# LDO_3V3.net
KiCad netlist of a schematic drawn in Altium Designer
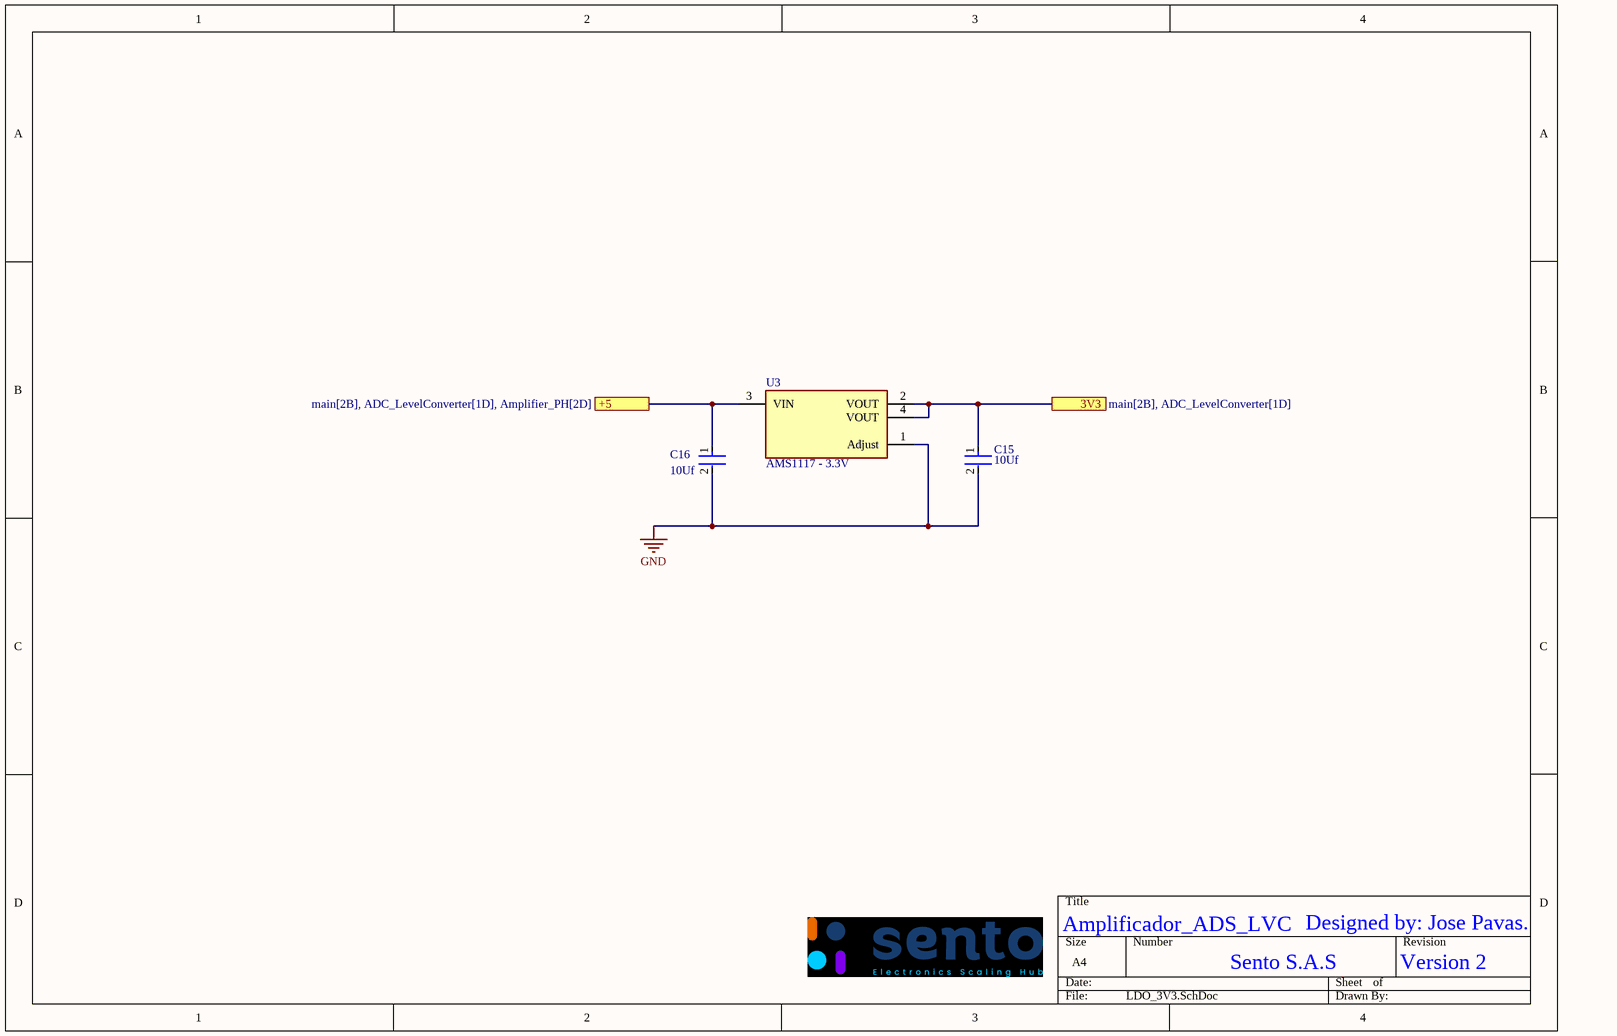
[diagram p0: LDO_3V3.SchDoc]

(export (version "E")
  (design (tool "Eeschema 10.0.6"))
  (components
    (comp (ref "C15")
      (value "10Uf")
      (footprint "FP-GRM188-0_1-e0_2_0_55-IPC_A")
      (description "Chip Multilayer Ceramic Capacitors for General Purpose, 0603, 10uF, X5R, 15%, 20%, 6.3V")
      (fields (field (name "VOLTAGE") "6.3V") (field (name "TOLERANCE") "20%"))
      (libsource (lib "Altium Content Vault") (part "02cd4be3c70576c341d710602a673aa"))
    )
    (comp (ref "C16")
      (value "10Uf")
      (footprint "FP-GRM188-0_1-e0_2_0_55-IPC_A")
      (description "Chip Multilayer Ceramic Capacitors for General Purpose, 0603, 10uF, X5R, 15%, 20%, 6.3V")
      (fields (field (name "VOLTAGE") "6.3V") (field (name "TOLERANCE") "20%"))
      (libsource (lib "Altium Content Vault") (part "02cd4be3c70576c341d710602a673aa"))
    )
    (comp (ref "U3")
      (value "AMS1117 - 3.3V")
      (footprint "FP-ams1117-IPC_C")
      (description "1A LOW DROPOUT VOLTAGE REGULATOR")
      (fields (field (name "LCSC PART NUMBER") "C5250992"))
      (libsource (lib "Altium Content Vault") (part "59ad430b93a2c51b3e6ee7c3b069677"))
    )
  )
  (nets
    (net (code "1") (name "/+5") (class "Default")
      (node (ref "C16") (pin "1") (pinfunction "1_1") (pintype "passive"))
      (node (ref "U3") (pin "3") (pinfunction "VIN_3") (pintype "power_in"))
    )
    (net (code "2") (name "/3V3") (class "Default")
      (node (ref "C15") (pin "1") (pinfunction "1_1") (pintype "passive"))
      (node (ref "U3") (pin "2") (pinfunction "VOUT_2") (pintype "passive"))
      (node (ref "U3") (pin "4") (pinfunction "VOUT_4") (pintype "passive"))
    )
    (net (code "3") (name "GND") (class "Default")
      (node (ref "C15") (pin "2") (pinfunction "2_2") (pintype "passive"))
      (node (ref "C16") (pin "2") (pinfunction "2_2") (pintype "passive"))
      (node (ref "U3") (pin "1") (pinfunction "Adjust_1") (pintype "passive"))
    )
  )
)
